# SCH_New-Projectp_2026-05-30.net
KiCad netlist of a schematic drawn in EasyEDA
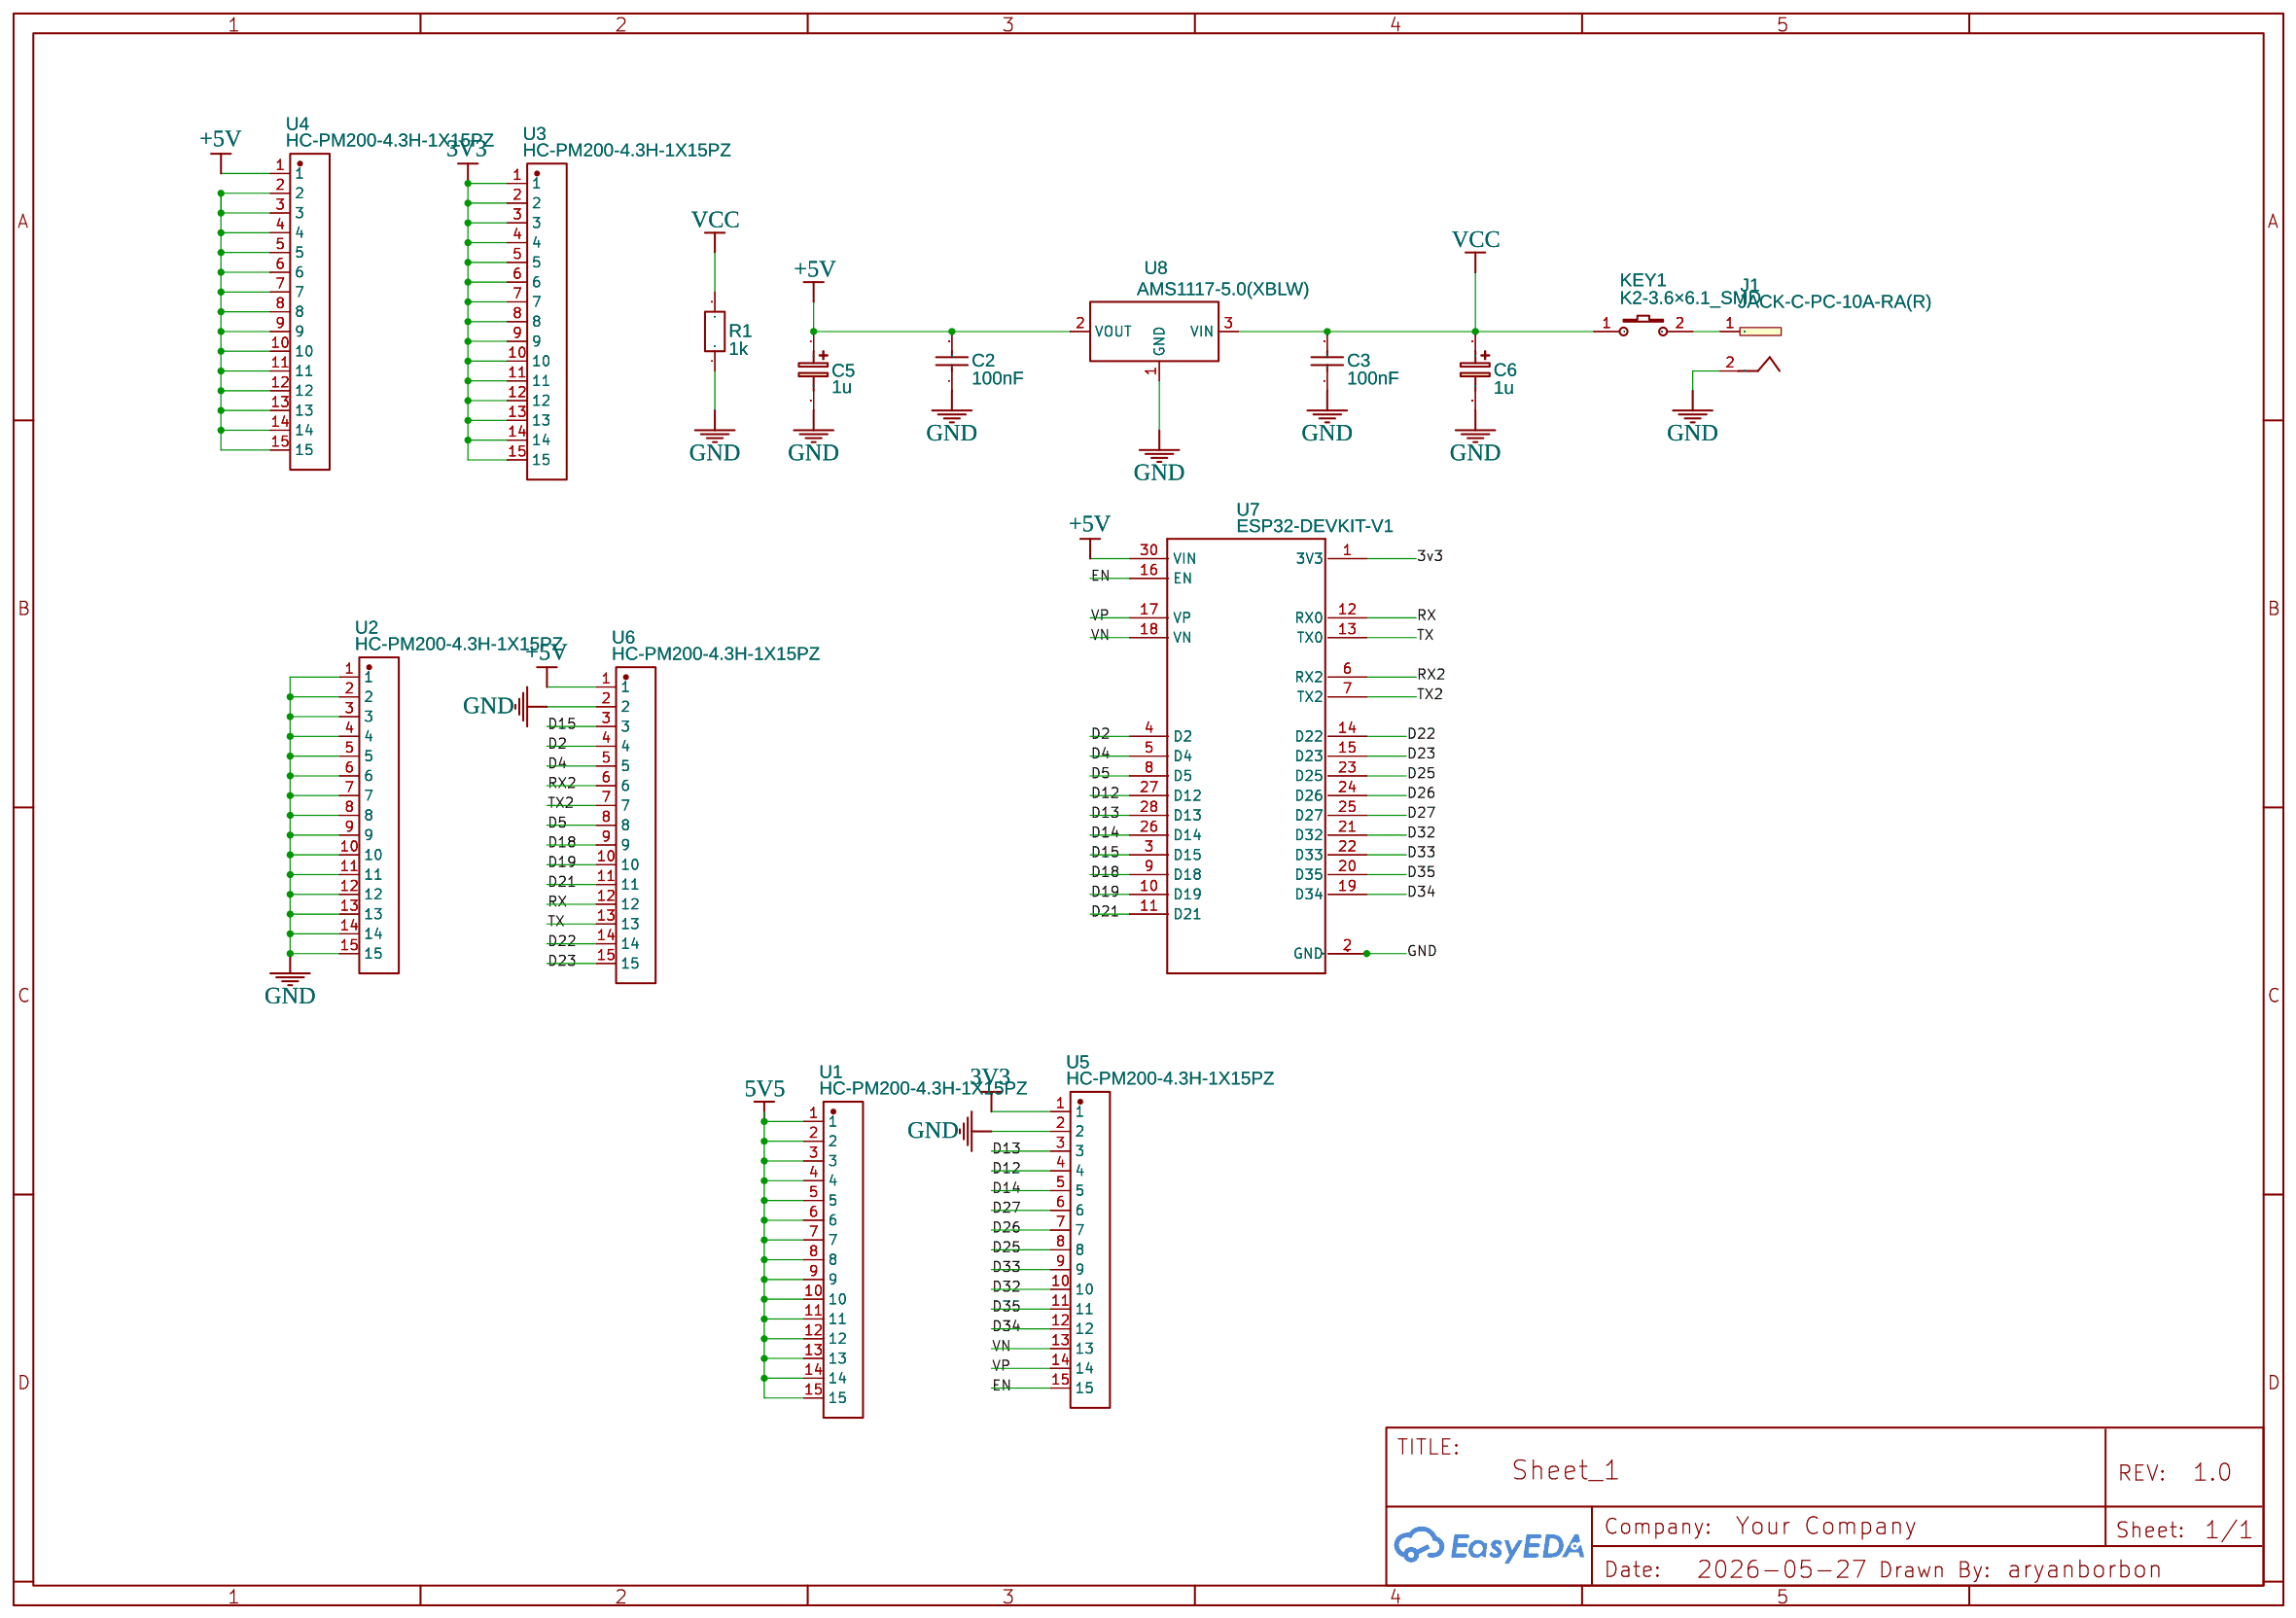
[diagram p0: schematic sheet]

(export (version "E")
  (design (tool "Eeschema 10.0.6"))
  (components
    (comp (ref "C2")
      (value "100nF")
      (fields (field (name "Manufacturer Part") "0.1UF(104) +-20% 63v"))
      (libsource (lib "") (part "100nF"))
    )
    (comp (ref "C3")
      (value "100nF")
      (fields (field (name "Manufacturer Part") "0.1UF(104) +-20% 63v"))
      (libsource (lib "") (part "100nF"))
    )
    (comp (ref "C5") (value "1u") (libsource (lib "") (part "C_Tan_SMD_A_EU_1")))
    (comp (ref "C6") (value "1u") (libsource (lib "") (part "C_Tan_SMD_A_EU")))
    (comp (ref "J1") (value "JACK-C-PC-10A-RA(R)") (libsource (lib "") (part "JACK-C-PC-10A-RA(R)")))
    (comp (ref "KEY1")
      (value "K2-3.6×6.1_SMD")
      (fields (field (name "Manufacturer Part") "K2-1107ST-A4SW-06"))
      (libsource (lib "") (part "K2-3.6×6.1_SMD"))
    )
    (comp (ref "R1") (value "1k") (libsource (lib "") (part "R_0603_EU")))
    (comp (ref "U1")
      (value "HC-PM200-4.3H-1X15PZ")
      (fields
        (field (name "Manufacturer Part") "HC-PM200-4.3H-1x15PZ")
        (field (name "Manufacturer") "HC(虹成电子)")
      )
      (libsource (lib "") (part "HC-PM200-4.3H-1X15PZ"))
    )
    (comp (ref "U2")
      (value "HC-PM200-4.3H-1X15PZ")
      (fields
        (field (name "Manufacturer Part") "HC-PM200-4.3H-1x15PZ")
        (field (name "Manufacturer") "HC(虹成电子)")
      )
      (libsource (lib "") (part "HC-PM200-4.3H-1X15PZ"))
    )
    (comp (ref "U3")
      (value "HC-PM200-4.3H-1X15PZ")
      (fields
        (field (name "Manufacturer Part") "HC-PM200-4.3H-1x15PZ")
        (field (name "Manufacturer") "HC(虹成电子)")
      )
      (libsource (lib "") (part "HC-PM200-4.3H-1X15PZ"))
    )
    (comp (ref "U4")
      (value "HC-PM200-4.3H-1X15PZ")
      (fields
        (field (name "Manufacturer Part") "HC-PM200-4.3H-1x15PZ")
        (field (name "Manufacturer") "HC(虹成电子)")
      )
      (libsource (lib "") (part "HC-PM200-4.3H-1X15PZ"))
    )
    (comp (ref "U5")
      (value "HC-PM200-4.3H-1X15PZ")
      (fields
        (field (name "Manufacturer Part") "HC-PM200-4.3H-1x15PZ")
        (field (name "Manufacturer") "HC(虹成电子)")
      )
      (libsource (lib "") (part "HC-PM200-4.3H-1X15PZ"))
    )
    (comp (ref "U6")
      (value "HC-PM200-4.3H-1X15PZ")
      (fields
        (field (name "Manufacturer Part") "HC-PM200-4.3H-1x15PZ")
        (field (name "Manufacturer") "HC(虹成电子)")
      )
      (libsource (lib "") (part "HC-PM200-4.3H-1X15PZ"))
    )
    (comp (ref "U7") (value "ESP32-DEVKIT-V1") (libsource (lib "") (part "ESP32-DEVKIT-V1")))
    (comp (ref "U8")
      (value "AMS1117-5.0(XBLW)")
      (fields (field (name "Manufacturer") "XBLW(芯伯乐)"))
      (libsource (lib "") (part "AMS1117-5.0(XBLW)"))
    )
  )
  (nets
    (net (code "1") (name "+5V") (class "Default")
      (node (ref "C2") (pin "2") (pinfunction "2_2") (pintype "input"))
      (node (ref "C5") (pin "1") (pinfunction "1_1") (pintype "unspecified"))
      (node (ref "U4") (pin "1") (pinfunction "1_1") (pintype "unspecified"))
      (node (ref "U6") (pin "1") (pinfunction "1_1") (pintype "unspecified"))
      (node (ref "U7") (pin "30") (pinfunction "VIN_30") (pintype "bidirectional"))
      (node (ref "U8") (pin "2") (pinfunction "VOUT_2") (pintype "unspecified"))
    )
    (net (code "2") (name "/3v3") (class "Default")
      (node (ref "U7") (pin "1") (pinfunction "3V3_1") (pintype "bidirectional"))
    )
    (net (code "3") (name "/D2") (class "Default")
      (node (ref "U6") (pin "4") (pinfunction "4_4") (pintype "unspecified"))
      (node (ref "U7") (pin "4") (pinfunction "D2_4") (pintype "bidirectional"))
    )
    (net (code "4") (name "/D4") (class "Default")
      (node (ref "U6") (pin "5") (pinfunction "5_5") (pintype "unspecified"))
      (node (ref "U7") (pin "5") (pinfunction "D4_5") (pintype "bidirectional"))
    )
    (net (code "5") (name "/D5") (class "Default")
      (node (ref "U6") (pin "8") (pinfunction "8_8") (pintype "unspecified"))
      (node (ref "U7") (pin "8") (pinfunction "D5_8") (pintype "bidirectional"))
    )
    (net (code "6") (name "/D12") (class "Default")
      (node (ref "U5") (pin "4") (pinfunction "4_4") (pintype "unspecified"))
      (node (ref "U7") (pin "27") (pinfunction "D12_27") (pintype "bidirectional"))
    )
    (net (code "7") (name "/D13") (class "Default")
      (node (ref "U5") (pin "3") (pinfunction "3_3") (pintype "unspecified"))
      (node (ref "U7") (pin "28") (pinfunction "D13_28") (pintype "bidirectional"))
    )
    (net (code "8") (name "/D14") (class "Default")
      (node (ref "U5") (pin "5") (pinfunction "5_5") (pintype "unspecified"))
      (node (ref "U7") (pin "26") (pinfunction "D14_26") (pintype "bidirectional"))
    )
    (net (code "9") (name "/D15") (class "Default")
      (node (ref "U6") (pin "3") (pinfunction "3_3") (pintype "unspecified"))
      (node (ref "U7") (pin "3") (pinfunction "D15_3") (pintype "bidirectional"))
    )
    (net (code "10") (name "/D18") (class "Default")
      (node (ref "U6") (pin "9") (pinfunction "9_9") (pintype "unspecified"))
      (node (ref "U7") (pin "9") (pinfunction "D18_9") (pintype "bidirectional"))
    )
    (net (code "11") (name "/D19") (class "Default")
      (node (ref "U6") (pin "10") (pinfunction "10_10") (pintype "unspecified"))
      (node (ref "U7") (pin "10") (pinfunction "D19_10") (pintype "bidirectional"))
    )
    (net (code "12") (name "/D21") (class "Default")
      (node (ref "U6") (pin "11") (pinfunction "11_11") (pintype "unspecified"))
      (node (ref "U7") (pin "11") (pinfunction "D21_11") (pintype "bidirectional"))
    )
    (net (code "13") (name "/D22") (class "Default")
      (node (ref "U6") (pin "14") (pinfunction "14_14") (pintype "unspecified"))
      (node (ref "U7") (pin "14") (pinfunction "D22_14") (pintype "bidirectional"))
    )
    (net (code "14") (name "/D23") (class "Default")
      (node (ref "U6") (pin "15") (pinfunction "15_15") (pintype "unspecified"))
      (node (ref "U7") (pin "15") (pinfunction "D23_15") (pintype "bidirectional"))
    )
    (net (code "15") (name "/D25") (class "Default")
      (node (ref "U5") (pin "8") (pinfunction "8_8") (pintype "unspecified"))
      (node (ref "U7") (pin "23") (pinfunction "D25_23") (pintype "bidirectional"))
    )
    (net (code "16") (name "/D26") (class "Default")
      (node (ref "U5") (pin "7") (pinfunction "7_7") (pintype "unspecified"))
      (node (ref "U7") (pin "24") (pinfunction "D26_24") (pintype "bidirectional"))
    )
    (net (code "17") (name "/D27") (class "Default")
      (node (ref "U5") (pin "6") (pinfunction "6_6") (pintype "unspecified"))
      (node (ref "U7") (pin "25") (pinfunction "D27_25") (pintype "bidirectional"))
    )
    (net (code "18") (name "/D32") (class "Default")
      (node (ref "U5") (pin "10") (pinfunction "10_10") (pintype "unspecified"))
      (node (ref "U7") (pin "21") (pinfunction "D32_21") (pintype "bidirectional"))
    )
    (net (code "19") (name "/D33") (class "Default")
      (node (ref "U5") (pin "9") (pinfunction "9_9") (pintype "unspecified"))
      (node (ref "U7") (pin "22") (pinfunction "D33_22") (pintype "bidirectional"))
    )
    (net (code "20") (name "/D34") (class "Default")
      (node (ref "U5") (pin "12") (pinfunction "12_12") (pintype "unspecified"))
      (node (ref "U7") (pin "19") (pinfunction "D34_19") (pintype "bidirectional"))
    )
    (net (code "21") (name "/D35") (class "Default")
      (node (ref "U5") (pin "11") (pinfunction "11_11") (pintype "unspecified"))
      (node (ref "U7") (pin "20") (pinfunction "D35_20") (pintype "bidirectional"))
    )
    (net (code "22") (name "/EN") (class "Default")
      (node (ref "U5") (pin "15") (pinfunction "15_15") (pintype "unspecified"))
      (node (ref "U7") (pin "16") (pinfunction "EN_16") (pintype "bidirectional"))
    )
    (net (code "23") (name "/RX") (class "Default")
      (node (ref "U6") (pin "12") (pinfunction "12_12") (pintype "unspecified"))
      (node (ref "U7") (pin "12") (pinfunction "RX0_12") (pintype "bidirectional"))
    )
    (net (code "24") (name "/RX2") (class "Default")
      (node (ref "U6") (pin "6") (pinfunction "6_6") (pintype "unspecified"))
      (node (ref "U7") (pin "6") (pinfunction "RX2_6") (pintype "bidirectional"))
    )
    (net (code "25") (name "/TX") (class "Default")
      (node (ref "U6") (pin "13") (pinfunction "13_13") (pintype "unspecified"))
      (node (ref "U7") (pin "13") (pinfunction "TX0_13") (pintype "bidirectional"))
    )
    (net (code "26") (name "/TX2") (class "Default")
      (node (ref "U6") (pin "7") (pinfunction "7_7") (pintype "unspecified"))
      (node (ref "U7") (pin "7") (pinfunction "TX2_7") (pintype "bidirectional"))
    )
    (net (code "27") (name "/VN") (class "Default")
      (node (ref "U5") (pin "13") (pinfunction "13_13") (pintype "unspecified"))
      (node (ref "U7") (pin "18") (pinfunction "VN_18") (pintype "bidirectional"))
    )
    (net (code "28") (name "/VP") (class "Default")
      (node (ref "U5") (pin "14") (pinfunction "14_14") (pintype "unspecified"))
      (node (ref "U7") (pin "17") (pinfunction "VP_17") (pintype "bidirectional"))
    )
    (net (code "29") (name "3V3") (class "Default")
      (node (ref "U3") (pin "1") (pinfunction "1_1") (pintype "unspecified"))
      (node (ref "U3") (pin "10") (pinfunction "10_10") (pintype "unspecified"))
      (node (ref "U3") (pin "11") (pinfunction "11_11") (pintype "unspecified"))
      (node (ref "U3") (pin "12") (pinfunction "12_12") (pintype "unspecified"))
      (node (ref "U3") (pin "13") (pinfunction "13_13") (pintype "unspecified"))
      (node (ref "U3") (pin "14") (pinfunction "14_14") (pintype "unspecified"))
      (node (ref "U3") (pin "15") (pinfunction "15_15") (pintype "unspecified"))
      (node (ref "U3") (pin "2") (pinfunction "2_2") (pintype "unspecified"))
      (node (ref "U3") (pin "3") (pinfunction "3_3") (pintype "unspecified"))
      (node (ref "U3") (pin "4") (pinfunction "4_4") (pintype "unspecified"))
      (node (ref "U3") (pin "5") (pinfunction "5_5") (pintype "unspecified"))
      (node (ref "U3") (pin "6") (pinfunction "6_6") (pintype "unspecified"))
      (node (ref "U3") (pin "7") (pinfunction "7_7") (pintype "unspecified"))
      (node (ref "U3") (pin "8") (pinfunction "8_8") (pintype "unspecified"))
      (node (ref "U3") (pin "9") (pinfunction "9_9") (pintype "unspecified"))
      (node (ref "U5") (pin "1") (pinfunction "1_1") (pintype "unspecified"))
    )
    (net (code "30") (name "5V5") (class "Default")
      (node (ref "U1") (pin "1") (pinfunction "1_1") (pintype "unspecified"))
      (node (ref "U1") (pin "10") (pinfunction "10_10") (pintype "unspecified"))
      (node (ref "U1") (pin "11") (pinfunction "11_11") (pintype "unspecified"))
      (node (ref "U1") (pin "12") (pinfunction "12_12") (pintype "unspecified"))
      (node (ref "U1") (pin "13") (pinfunction "13_13") (pintype "unspecified"))
      (node (ref "U1") (pin "14") (pinfunction "14_14") (pintype "unspecified"))
      (node (ref "U1") (pin "15") (pinfunction "15_15") (pintype "unspecified"))
      (node (ref "U1") (pin "2") (pinfunction "2_2") (pintype "unspecified"))
      (node (ref "U1") (pin "3") (pinfunction "3_3") (pintype "unspecified"))
      (node (ref "U1") (pin "4") (pinfunction "4_4") (pintype "unspecified"))
      (node (ref "U1") (pin "5") (pinfunction "5_5") (pintype "unspecified"))
      (node (ref "U1") (pin "6") (pinfunction "6_6") (pintype "unspecified"))
      (node (ref "U1") (pin "7") (pinfunction "7_7") (pintype "unspecified"))
      (node (ref "U1") (pin "8") (pinfunction "8_8") (pintype "unspecified"))
      (node (ref "U1") (pin "9") (pinfunction "9_9") (pintype "unspecified"))
    )
    (net (code "31") (name "GND") (class "Default")
      (node (ref "C2") (pin "1") (pinfunction "1_1") (pintype "input"))
      (node (ref "C3") (pin "1") (pinfunction "1_1") (pintype "input"))
      (node (ref "C5") (pin "2") (pinfunction "2_2") (pintype "unspecified"))
      (node (ref "C6") (pin "2") (pinfunction "2_2") (pintype "unspecified"))
      (node (ref "J1") (pin "2") (pinfunction "2_2") (pintype "bidirectional"))
      (node (ref "R1") (pin "1") (pinfunction "1_1") (pintype "unspecified"))
      (node (ref "U2") (pin "1") (pinfunction "1_1") (pintype "unspecified"))
      (node (ref "U2") (pin "10") (pinfunction "10_10") (pintype "unspecified"))
      (node (ref "U2") (pin "11") (pinfunction "11_11") (pintype "unspecified"))
      (node (ref "U2") (pin "12") (pinfunction "12_12") (pintype "unspecified"))
      (node (ref "U2") (pin "13") (pinfunction "13_13") (pintype "unspecified"))
      (node (ref "U2") (pin "14") (pinfunction "14_14") (pintype "unspecified"))
      (node (ref "U2") (pin "15") (pinfunction "15_15") (pintype "unspecified"))
      (node (ref "U2") (pin "2") (pinfunction "2_2") (pintype "unspecified"))
      (node (ref "U2") (pin "3") (pinfunction "3_3") (pintype "unspecified"))
      (node (ref "U2") (pin "4") (pinfunction "4_4") (pintype "unspecified"))
      (node (ref "U2") (pin "5") (pinfunction "5_5") (pintype "unspecified"))
      (node (ref "U2") (pin "6") (pinfunction "6_6") (pintype "unspecified"))
      (node (ref "U2") (pin "7") (pinfunction "7_7") (pintype "unspecified"))
      (node (ref "U2") (pin "8") (pinfunction "8_8") (pintype "unspecified"))
      (node (ref "U2") (pin "9") (pinfunction "9_9") (pintype "unspecified"))
      (node (ref "U5") (pin "2") (pinfunction "2_2") (pintype "unspecified"))
      (node (ref "U6") (pin "2") (pinfunction "2_2") (pintype "unspecified"))
      (node (ref "U7") (pin "2") (pinfunction "GND_2") (pintype "bidirectional"))
      (node (ref "U7") (pin "29") (pinfunction "GND_29") (pintype "bidirectional"))
      (node (ref "U8") (pin "1") (pinfunction "GND_1") (pintype "unspecified"))
    )
    (net (code "32") (name "Net-(J1-Pad1)") (class "Default")
      (node (ref "J1") (pin "1") (pinfunction "1_1") (pintype "bidirectional"))
      (node (ref "KEY1") (pin "2") (pinfunction "2_2") (pintype "unspecified"))
    )
    (net (code "33") (name "Net-(U4-Pad10)") (class "Default")
      (node (ref "U4") (pin "10") (pinfunction "10_10") (pintype "unspecified"))
      (node (ref "U4") (pin "11") (pinfunction "11_11") (pintype "unspecified"))
      (node (ref "U4") (pin "12") (pinfunction "12_12") (pintype "unspecified"))
      (node (ref "U4") (pin "13") (pinfunction "13_13") (pintype "unspecified"))
      (node (ref "U4") (pin "14") (pinfunction "14_14") (pintype "unspecified"))
      (node (ref "U4") (pin "15") (pinfunction "15_15") (pintype "unspecified"))
      (node (ref "U4") (pin "2") (pinfunction "2_2") (pintype "unspecified"))
      (node (ref "U4") (pin "3") (pinfunction "3_3") (pintype "unspecified"))
      (node (ref "U4") (pin "4") (pinfunction "4_4") (pintype "unspecified"))
      (node (ref "U4") (pin "5") (pinfunction "5_5") (pintype "unspecified"))
      (node (ref "U4") (pin "6") (pinfunction "6_6") (pintype "unspecified"))
      (node (ref "U4") (pin "7") (pinfunction "7_7") (pintype "unspecified"))
      (node (ref "U4") (pin "8") (pinfunction "8_8") (pintype "unspecified"))
      (node (ref "U4") (pin "9") (pinfunction "9_9") (pintype "unspecified"))
    )
    (net (code "34") (name "VCC") (class "Default")
      (node (ref "C3") (pin "2") (pinfunction "2_2") (pintype "input"))
      (node (ref "C6") (pin "1") (pinfunction "1_1") (pintype "unspecified"))
      (node (ref "KEY1") (pin "1") (pinfunction "1_1") (pintype "unspecified"))
      (node (ref "R1") (pin "2") (pinfunction "2_2") (pintype "unspecified"))
      (node (ref "U8") (pin "3") (pinfunction "VIN_3") (pintype "unspecified"))
    )
  )
)
